# Power.net
KiCad netlist of a schematic drawn in Altium Designer
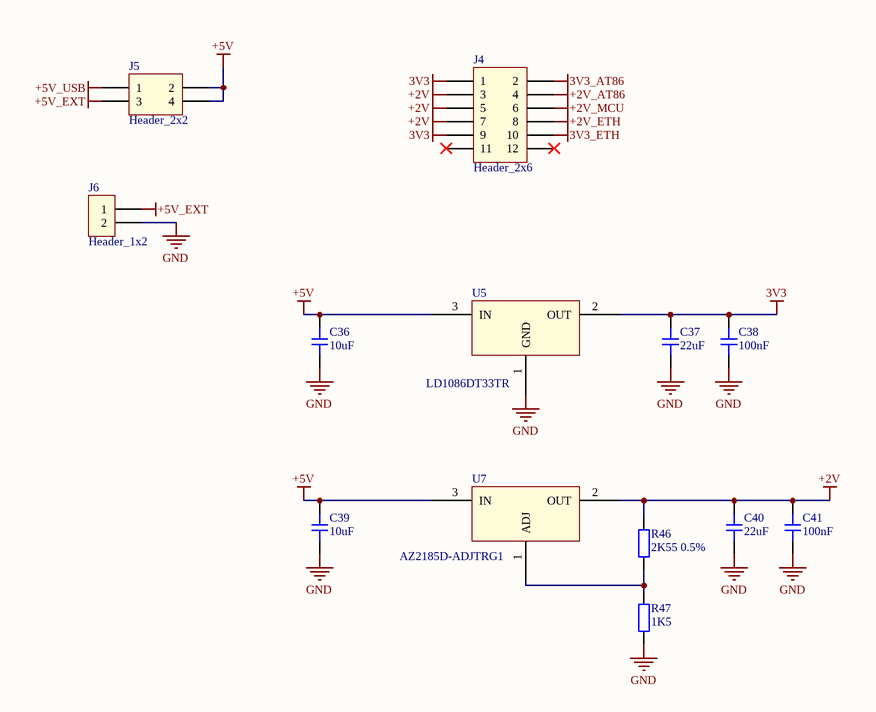
[diagram p0: Power.SchDoc]

(export (version "E")
  (design (tool "Eeschema 10.0.6"))
  (components
    (comp (ref "C36")
      (value "10uF")
      (footprint "Capacitor-1210")
      (fields (field (name "Comment") "C-10uF-1210"))
      (libsource (lib "Components") (part "C-10uF-1210"))
    )
    (comp (ref "C37")
      (value "22uF")
      (footprint "Capacitor-1210")
      (fields (field (name "Comment") "C-22uF-1210"))
      (libsource (lib "Components") (part "C-22uF-1210"))
    )
    (comp (ref "C38")
      (value "100nF")
      (footprint "Capacitor-0603")
      (fields (field (name "Comment") "C-100nF-0603"))
      (libsource (lib "Components") (part "C-100nF-0603"))
    )
    (comp (ref "C39")
      (value "10uF")
      (footprint "Capacitor-1210")
      (fields (field (name "Comment") "C-10uF-1210"))
      (libsource (lib "Components") (part "C-10uF-1210"))
    )
    (comp (ref "C40")
      (value "22uF")
      (footprint "Capacitor-1210")
      (fields (field (name "Comment") "C-22uF-1210"))
      (libsource (lib "Components") (part "C-22uF-1210"))
    )
    (comp (ref "C41")
      (value "100nF")
      (footprint "Capacitor-0603")
      (fields (field (name "Comment") "C-100nF-0603"))
      (libsource (lib "Components") (part "C-100nF-0603"))
    )
    (comp (ref "J4")
      (value "Header_2x6")
      (footprint "Header_2x6")
      (libsource (lib "Components") (part "Header_2x6"))
    )
    (comp (ref "J5")
      (value "Header_2x2")
      (footprint "Header_2x2")
      (libsource (lib "Components") (part "Header_2x2"))
    )
    (comp (ref "J6")
      (value "Header_1x2")
      (footprint "Header_1x2")
      (libsource (lib "Components") (part "Header_1x2"))
    )
    (comp (ref "R46")
      (value "2K55 0.5%")
      (footprint "Resistor-0603")
      (fields (field (name "Comment") "R-2K55-0603"))
      (libsource (lib "Components") (part "R-2K55-0603"))
    )
    (comp (ref "R47")
      (value "1K5")
      (footprint "Resistor-0603")
      (fields (field (name "Comment") "R-1K5-0603"))
      (libsource (lib "Components") (part "R-1K5-0603"))
    )
    (comp (ref "U5")
      (value "LD1086DT33TR")
      (footprint "LD1086DT33TR")
      (libsource (lib "Components") (part "LD1086DT33TR"))
    )
    (comp (ref "U7")
      (value "AZ2185D-ADJTRG1")
      (footprint "AZ2185D-ADJTRG1")
      (libsource (lib "Components") (part "AZ2185D-ADJTRG1"))
    )
  )
  (nets
    (net (code "1") (name "+2V") (class "Default")
      (node (ref "C40") (pin "2") (pinfunction "2_2") (pintype "passive"))
      (node (ref "C41") (pin "2") (pinfunction "2_2") (pintype "passive"))
      (node (ref "J4") (pin "3") (pinfunction "3_3") (pintype "passive"))
      (node (ref "J4") (pin "5") (pinfunction "5_5") (pintype "passive"))
      (node (ref "J4") (pin "7") (pinfunction "7_7") (pintype "passive"))
      (node (ref "R46") (pin "2") (pinfunction "2_2") (pintype "passive"))
      (node (ref "U7") (pin "2") (pinfunction "OUT_2") (pintype "passive"))
    )
    (net (code "2") (name "+2V_AT86") (class "Default")
      (node (ref "J4") (pin "4") (pinfunction "4_4") (pintype "passive"))
    )
    (net (code "3") (name "+2V_ETH") (class "Default")
      (node (ref "J4") (pin "8") (pinfunction "8_8") (pintype "passive"))
    )
    (net (code "4") (name "+2V_MCU") (class "Default")
      (node (ref "J4") (pin "6") (pinfunction "6_6") (pintype "passive"))
    )
    (net (code "5") (name "+5V") (class "Default")
      (node (ref "C36") (pin "2") (pinfunction "2_2") (pintype "passive"))
      (node (ref "C39") (pin "2") (pinfunction "2_2") (pintype "passive"))
      (node (ref "J5") (pin "2") (pinfunction "2_2") (pintype "passive"))
      (node (ref "J5") (pin "4") (pinfunction "4_4") (pintype "passive"))
      (node (ref "U5") (pin "3") (pinfunction "IN_3") (pintype "passive"))
      (node (ref "U7") (pin "3") (pinfunction "IN_3") (pintype "passive"))
    )
    (net (code "6") (name "+5V_EXT") (class "Default")
      (node (ref "J5") (pin "3") (pinfunction "3_3") (pintype "passive"))
      (node (ref "J6") (pin "1") (pinfunction "1_1") (pintype "passive"))
    )
    (net (code "7") (name "+5V_USB") (class "Default")
      (node (ref "J5") (pin "1") (pinfunction "1_1") (pintype "passive"))
    )
    (net (code "8") (name "3V3") (class "Default")
      (node (ref "C37") (pin "2") (pinfunction "2_2") (pintype "passive"))
      (node (ref "C38") (pin "2") (pinfunction "2_2") (pintype "passive"))
      (node (ref "J4") (pin "1") (pinfunction "1_1") (pintype "passive"))
      (node (ref "J4") (pin "9") (pinfunction "9_9") (pintype "passive"))
      (node (ref "U5") (pin "2") (pinfunction "OUT_2") (pintype "passive"))
    )
    (net (code "9") (name "3V3_AT86") (class "Default")
      (node (ref "J4") (pin "2") (pinfunction "2_2") (pintype "passive"))
    )
    (net (code "10") (name "3V3_ETH") (class "Default")
      (node (ref "J4") (pin "10") (pinfunction "10_10") (pintype "passive"))
    )
    (net (code "11") (name "GND") (class "Default")
      (node (ref "C36") (pin "1") (pinfunction "1_1") (pintype "passive"))
      (node (ref "C37") (pin "1") (pinfunction "1_1") (pintype "passive"))
      (node (ref "C38") (pin "1") (pinfunction "1_1") (pintype "passive"))
      (node (ref "C39") (pin "1") (pinfunction "1_1") (pintype "passive"))
      (node (ref "C40") (pin "1") (pinfunction "1_1") (pintype "passive"))
      (node (ref "C41") (pin "1") (pinfunction "1_1") (pintype "passive"))
      (node (ref "J6") (pin "2") (pinfunction "2_2") (pintype "passive"))
      (node (ref "R47") (pin "1") (pinfunction "1_1") (pintype "passive"))
      (node (ref "U5") (pin "1") (pinfunction "GND_1") (pintype "passive"))
    )
    (net (code "12") (name "Net-(U7-ADJ)") (class "Default")
      (node (ref "R46") (pin "1") (pinfunction "1_1") (pintype "passive"))
      (node (ref "R47") (pin "2") (pinfunction "2_2") (pintype "passive"))
      (node (ref "U7") (pin "1") (pinfunction "ADJ_1") (pintype "passive"))
    )
    (net (code "13") (name "unconnected-(J4-Pad11)") (class "Default")
      (node (ref "J4") (pin "11") (pinfunction "11_11") (pintype "passive+no_connect"))
    )
    (net (code "14") (name "unconnected-(J4-Pad12)") (class "Default")
      (node (ref "J4") (pin "12") (pinfunction "12_12") (pintype "passive+no_connect"))
    )
  )
)
